# pyro_driver.net
KiCad netlist of a schematic drawn in EAGLE
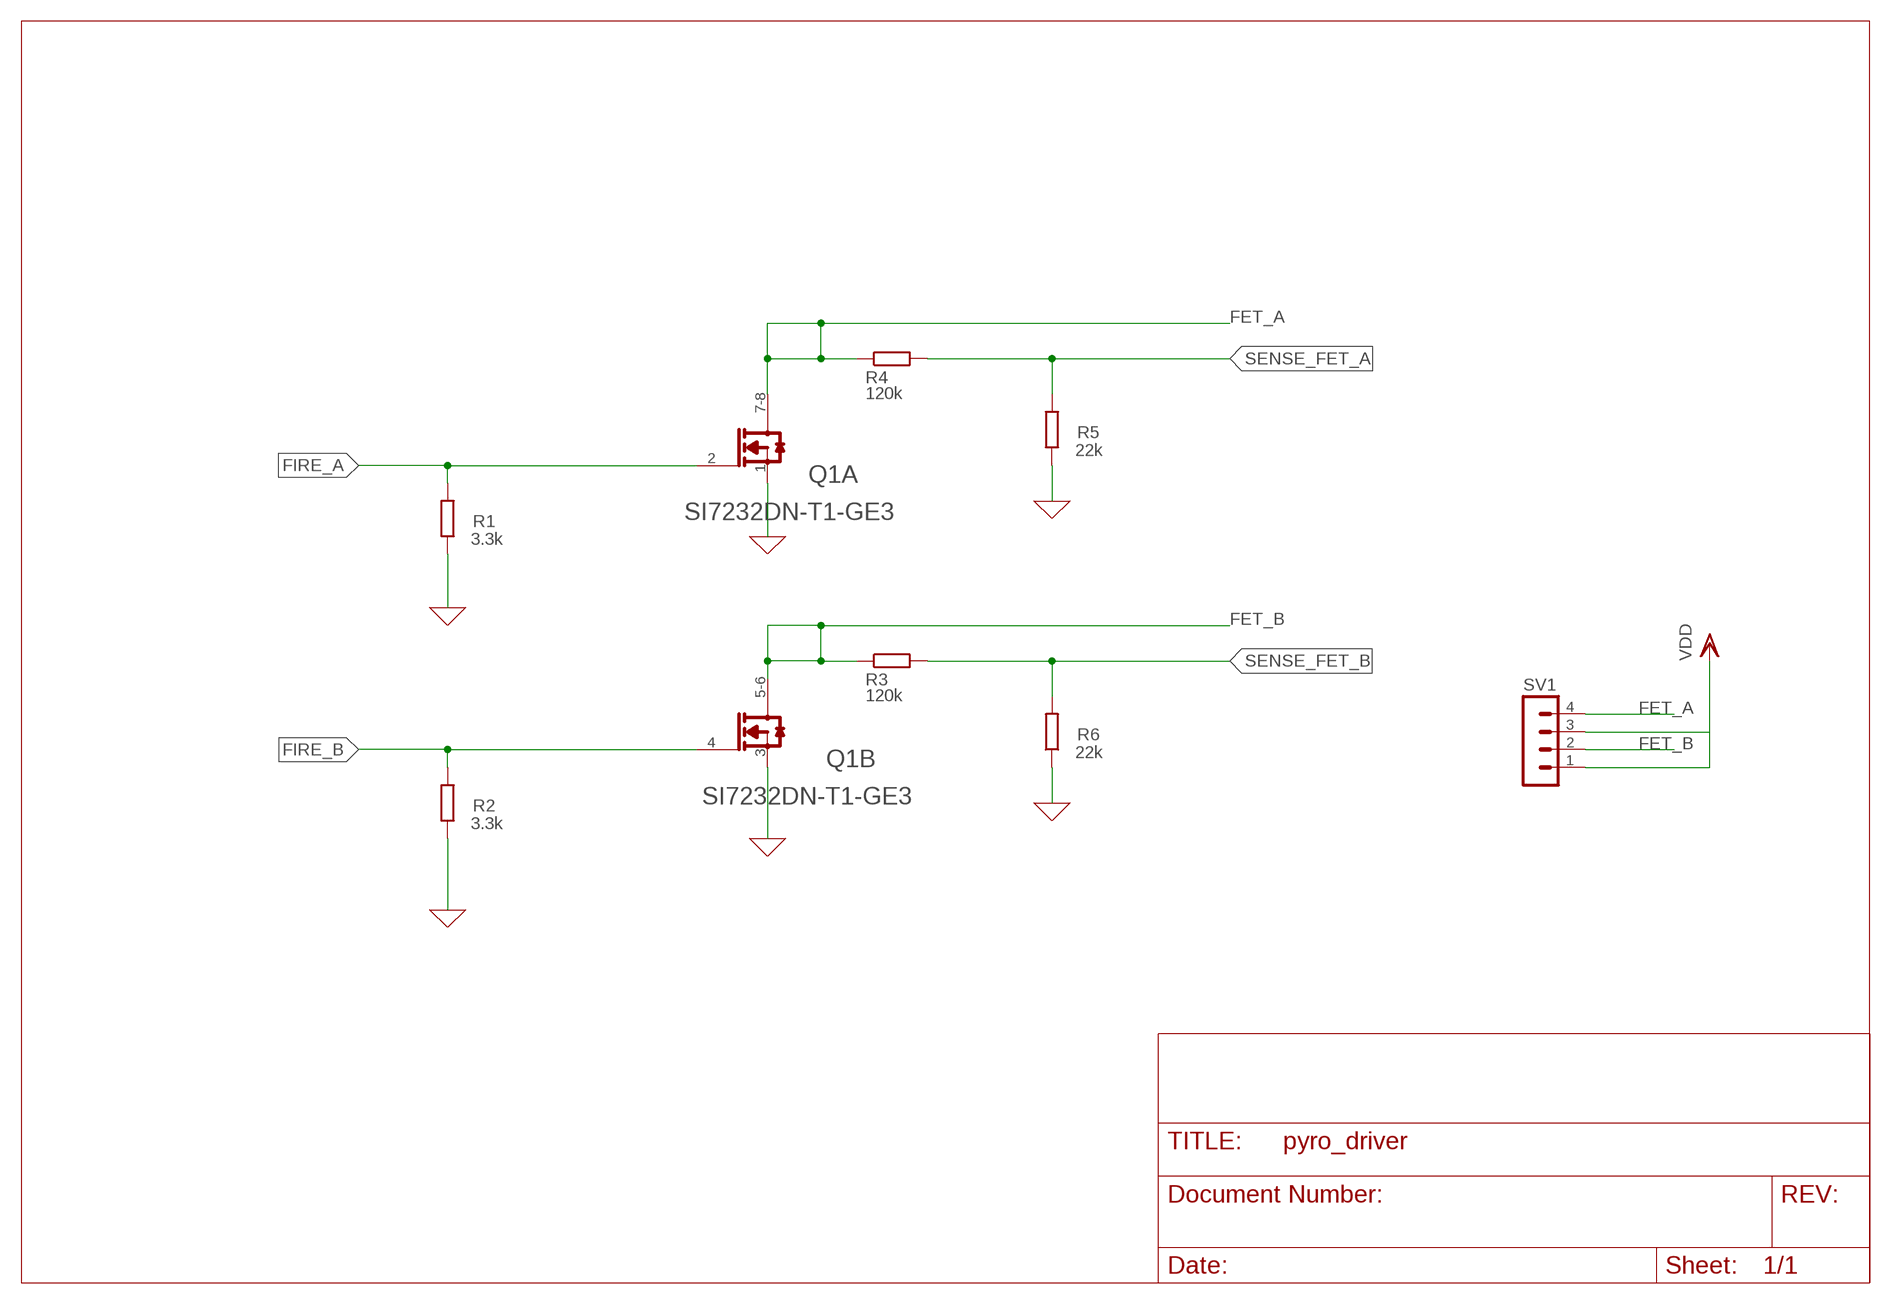
[diagram p0: schematic, sheet 1]

(export (version "E")
  (design (tool "Eeschema 10.0.6"))
  (components
    (comp (ref "Q1")
      (value "VISHAY_SI7232DN-T1-GE3VISHAY_SI7232DN-T1-GE3_0_0")
      (footprint "eagle-import:VISHAY_SI7232DN-T1-GE3_0")
      (fields
        (field (name "DIGIKEY_PART_NUMBER") "SI7232DN-T1-GE3CT-ND")
        (field (name "MF") "Vishay")
        (field (name "MOUSER_PART_NUMBER") "781-SI7232DN-GE3")
      )
      (libsource (lib "eagle-import") (part "VISHAY_SI7232DN-T1-GE3VISHAY_SI7232DN-T1-GE3_0_0"))
    )
    (comp (ref "R1")
      (value "3.3k")
      (footprint "eagle-import:R0603")
      (libsource (lib "eagle-import") (part "R-EU_R0603"))
    )
    (comp (ref "R2")
      (value "3.3k")
      (footprint "eagle-import:R0603")
      (libsource (lib "eagle-import") (part "R-EU_R0603"))
    )
    (comp (ref "R3")
      (value "120k")
      (footprint "eagle-import:R0603")
      (libsource (lib "eagle-import") (part "R-EU_R0603"))
    )
    (comp (ref "R4")
      (value "120k")
      (footprint "eagle-import:R0603")
      (libsource (lib "eagle-import") (part "R-EU_R0603"))
    )
    (comp (ref "R5")
      (value "22k")
      (footprint "eagle-import:R0603")
      (libsource (lib "eagle-import") (part "R-EU_R0603"))
    )
    (comp (ref "R6")
      (value "22k")
      (footprint "eagle-import:R0603")
      (libsource (lib "eagle-import") (part "R-EU_R0603"))
    )
    (comp (ref "SV1")
      (value "MA04-1")
      (footprint "eagle-import:MA04-1")
      (libsource (lib "eagle-import") (part "MA04-1"))
    )
  )
  (nets
    (net (code "1") (name "/FET_A") (class "Default")
      (node (ref "Q1") (pin "7-8") (pinfunction "D1_7-8") (pintype "passive"))
      (node (ref "R4") (pin "1") (pinfunction "1_1") (pintype "passive"))
      (node (ref "SV1") (pin "4") (pinfunction "4_4") (pintype "passive"))
    )
    (net (code "2") (name "/FET_B") (class "Default")
      (node (ref "Q1") (pin "5-6") (pinfunction "D2_5-6") (pintype "passive"))
      (node (ref "R3") (pin "1") (pinfunction "1_1") (pintype "passive"))
      (node (ref "SV1") (pin "2") (pinfunction "2_2") (pintype "passive"))
    )
    (net (code "3") (name "FIRE_A") (class "Default")
      (node (ref "Q1") (pin "2") (pinfunction "G1_2") (pintype "passive"))
      (node (ref "R1") (pin "2") (pinfunction "2_2") (pintype "passive"))
    )
    (net (code "4") (name "FIRE_B") (class "Default")
      (node (ref "Q1") (pin "4") (pinfunction "G2_4") (pintype "passive"))
      (node (ref "R2") (pin "2") (pinfunction "2_2") (pintype "passive"))
    )
    (net (code "5") (name "GND") (class "Default")
      (node (ref "Q1") (pin "1") (pinfunction "S1_1") (pintype "passive"))
      (node (ref "Q1") (pin "3") (pinfunction "S2_3") (pintype "passive"))
      (node (ref "R1") (pin "1") (pinfunction "1_1") (pintype "passive"))
      (node (ref "R2") (pin "1") (pinfunction "1_1") (pintype "passive"))
      (node (ref "R5") (pin "1") (pinfunction "1_1") (pintype "passive"))
      (node (ref "R6") (pin "1") (pinfunction "1_1") (pintype "passive"))
    )
    (net (code "6") (name "SENSE_FET_A") (class "Default")
      (node (ref "R4") (pin "2") (pinfunction "2_2") (pintype "passive"))
      (node (ref "R5") (pin "2") (pinfunction "2_2") (pintype "passive"))
    )
    (net (code "7") (name "SENSE_FET_B") (class "Default")
      (node (ref "R3") (pin "2") (pinfunction "2_2") (pintype "passive"))
      (node (ref "R6") (pin "2") (pinfunction "2_2") (pintype "passive"))
    )
    (net (code "8") (name "VDD") (class "Default")
      (node (ref "SV1") (pin "1") (pinfunction "1_1") (pintype "passive"))
      (node (ref "SV1") (pin "3") (pinfunction "3_3") (pintype "passive"))
    )
  )
)
